# sevseg_driver.net
KiCad netlist of a schematic drawn in EAGLE
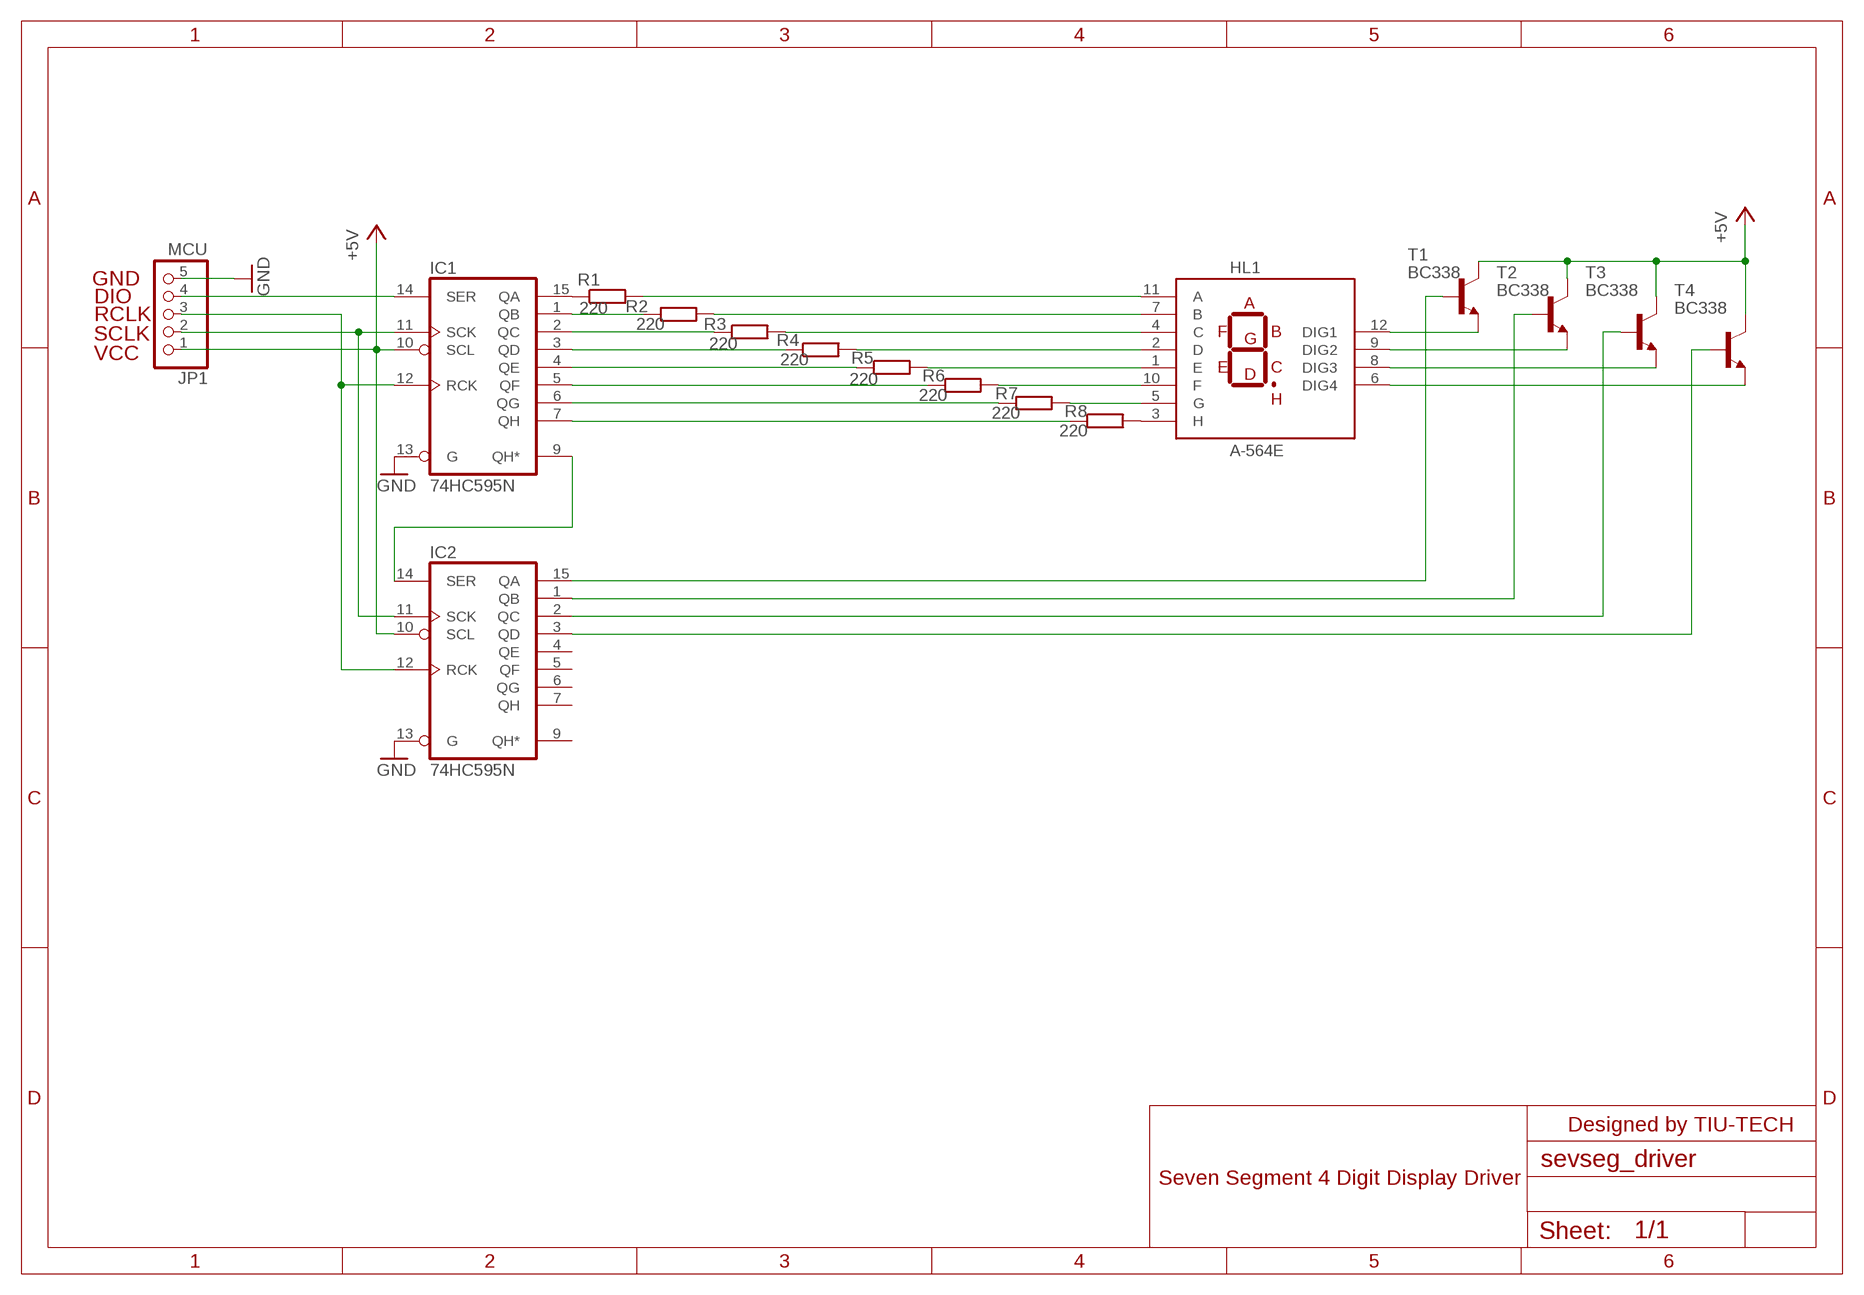
[diagram p0: schematic, sheet 1]

(export (version "E")
  (design (tool "Eeschema 10.0.6"))
  (components
    (comp (ref "HL1")
      (value "A-564E")
      (footprint "eagle-import:C_A-564")
      (libsource (lib "eagle-import") (part "A-564E"))
    )
    (comp (ref "IC1")
      (value "74HC595N")
      (footprint "eagle-import:DIL16")
      (libsource (lib "eagle-import") (part "74595NHC"))
    )
    (comp (ref "IC2")
      (value "74HC595N")
      (footprint "eagle-import:DIL16")
      (libsource (lib "eagle-import") (part "74595NHC"))
    )
    (comp (ref "JP1")
      (value "MCU")
      (footprint "eagle-import:1X05")
      (libsource (lib "eagle-import") (part "PINHD-1X5"))
    )
    (comp (ref "R1")
      (value "220")
      (footprint "eagle-import:0204_7")
      (libsource (lib "eagle-import") (part "R-EU_0204/7"))
    )
    (comp (ref "R2")
      (value "220")
      (footprint "eagle-import:0204_7")
      (libsource (lib "eagle-import") (part "R-EU_0204/7"))
    )
    (comp (ref "R3")
      (value "220")
      (footprint "eagle-import:0204_7")
      (libsource (lib "eagle-import") (part "R-EU_0204/7"))
    )
    (comp (ref "R4")
      (value "220")
      (footprint "eagle-import:0204_7")
      (libsource (lib "eagle-import") (part "R-EU_0204/7"))
    )
    (comp (ref "R5")
      (value "220")
      (footprint "eagle-import:0204_7")
      (libsource (lib "eagle-import") (part "R-EU_0204/7"))
    )
    (comp (ref "R6")
      (value "220")
      (footprint "eagle-import:0204_7")
      (libsource (lib "eagle-import") (part "R-EU_0204/7"))
    )
    (comp (ref "R7")
      (value "220")
      (footprint "eagle-import:0204_7")
      (libsource (lib "eagle-import") (part "R-EU_0204/7"))
    )
    (comp (ref "R8")
      (value "220")
      (footprint "eagle-import:0204_7")
      (libsource (lib "eagle-import") (part "R-EU_0204/7"))
    )
    (comp (ref "T1")
      (value "BC338")
      (footprint "eagle-import:TO92-EBC")
      (libsource (lib "eagle-import") (part "BC338"))
    )
    (comp (ref "T2")
      (value "BC338")
      (footprint "eagle-import:TO92-EBC")
      (libsource (lib "eagle-import") (part "BC338"))
    )
    (comp (ref "T3")
      (value "BC338")
      (footprint "eagle-import:TO92-EBC")
      (libsource (lib "eagle-import") (part "BC338"))
    )
    (comp (ref "T4")
      (value "BC338")
      (footprint "eagle-import:TO92-EBC")
      (libsource (lib "eagle-import") (part "BC338"))
    )
  )
  (nets
    (net (code "1") (name "+5V") (class "Default")
      (node (ref "IC1") (pin "10") (pinfunction "SCL_10") (pintype "input"))
      (node (ref "IC2") (pin "10") (pinfunction "SCL_10") (pintype "input"))
      (node (ref "JP1") (pin "1") (pinfunction "1_1") (pintype "passive"))
      (node (ref "T1") (pin "C") (pinfunction "C_C") (pintype "passive"))
      (node (ref "T2") (pin "C") (pinfunction "C_C") (pintype "passive"))
      (node (ref "T3") (pin "C") (pinfunction "C_C") (pintype "passive"))
      (node (ref "T4") (pin "C") (pinfunction "C_C") (pintype "passive"))
    )
    (net (code "2") (name "GND") (class "Default")
      (node (ref "IC1") (pin "13") (pinfunction "G_13") (pintype "input"))
      (node (ref "IC2") (pin "13") (pinfunction "G_13") (pintype "input"))
      (node (ref "JP1") (pin "5") (pinfunction "5_5") (pintype "passive"))
    )
    (net (code "3") (name "Net-(HL1-A)") (class "Default")
      (node (ref "HL1") (pin "11") (pinfunction "A_11") (pintype "input"))
      (node (ref "R1") (pin "2") (pinfunction "2_2") (pintype "passive"))
    )
    (net (code "4") (name "Net-(HL1-B)") (class "Default")
      (node (ref "HL1") (pin "7") (pinfunction "B_7") (pintype "input"))
      (node (ref "R2") (pin "2") (pinfunction "2_2") (pintype "passive"))
    )
    (net (code "5") (name "Net-(HL1-C)") (class "Default")
      (node (ref "HL1") (pin "4") (pinfunction "C_4") (pintype "input"))
      (node (ref "R3") (pin "2") (pinfunction "2_2") (pintype "passive"))
    )
    (net (code "6") (name "Net-(HL1-D)") (class "Default")
      (node (ref "HL1") (pin "2") (pinfunction "D_2") (pintype "input"))
      (node (ref "R4") (pin "2") (pinfunction "2_2") (pintype "passive"))
    )
    (net (code "7") (name "Net-(HL1-DIG1)") (class "Default")
      (node (ref "HL1") (pin "12") (pinfunction "DIG1_12") (pintype "input"))
      (node (ref "T1") (pin "E") (pinfunction "E_E") (pintype "passive"))
    )
    (net (code "8") (name "Net-(HL1-DIG2)") (class "Default")
      (node (ref "HL1") (pin "9") (pinfunction "DIG2_9") (pintype "input"))
      (node (ref "T2") (pin "E") (pinfunction "E_E") (pintype "passive"))
    )
    (net (code "9") (name "Net-(HL1-DIG3)") (class "Default")
      (node (ref "HL1") (pin "8") (pinfunction "DIG3_8") (pintype "input"))
      (node (ref "T3") (pin "E") (pinfunction "E_E") (pintype "passive"))
    )
    (net (code "10") (name "Net-(HL1-DIG4)") (class "Default")
      (node (ref "HL1") (pin "6") (pinfunction "DIG4_6") (pintype "input"))
      (node (ref "T4") (pin "E") (pinfunction "E_E") (pintype "passive"))
    )
    (net (code "11") (name "Net-(HL1-E)") (class "Default")
      (node (ref "HL1") (pin "1") (pinfunction "E_1") (pintype "input"))
      (node (ref "R5") (pin "2") (pinfunction "2_2") (pintype "passive"))
    )
    (net (code "12") (name "Net-(HL1-F)") (class "Default")
      (node (ref "HL1") (pin "10") (pinfunction "F_10") (pintype "input"))
      (node (ref "R6") (pin "2") (pinfunction "2_2") (pintype "passive"))
    )
    (net (code "13") (name "Net-(HL1-G)") (class "Default")
      (node (ref "HL1") (pin "5") (pinfunction "G_5") (pintype "input"))
      (node (ref "R7") (pin "2") (pinfunction "2_2") (pintype "passive"))
    )
    (net (code "14") (name "Net-(HL1-H)") (class "Default")
      (node (ref "HL1") (pin "3") (pinfunction "H_3") (pintype "input"))
      (node (ref "R8") (pin "2") (pinfunction "2_2") (pintype "passive"))
    )
    (net (code "15") (name "Net-(IC1A-QA)") (class "Default")
      (node (ref "IC1") (pin "15") (pinfunction "QA_15") (pintype "tri_state"))
      (node (ref "R1") (pin "1") (pinfunction "1_1") (pintype "passive"))
    )
    (net (code "16") (name "Net-(IC1A-QB)") (class "Default")
      (node (ref "IC1") (pin "1") (pinfunction "QB_1") (pintype "tri_state"))
      (node (ref "R2") (pin "1") (pinfunction "1_1") (pintype "passive"))
    )
    (net (code "17") (name "Net-(IC1A-QC)") (class "Default")
      (node (ref "IC1") (pin "2") (pinfunction "QC_2") (pintype "tri_state"))
      (node (ref "R3") (pin "1") (pinfunction "1_1") (pintype "passive"))
    )
    (net (code "18") (name "Net-(IC1A-QD)") (class "Default")
      (node (ref "IC1") (pin "3") (pinfunction "QD_3") (pintype "tri_state"))
      (node (ref "R4") (pin "1") (pinfunction "1_1") (pintype "passive"))
    )
    (net (code "19") (name "Net-(IC1A-QE)") (class "Default")
      (node (ref "IC1") (pin "4") (pinfunction "QE_4") (pintype "tri_state"))
      (node (ref "R5") (pin "1") (pinfunction "1_1") (pintype "passive"))
    )
    (net (code "20") (name "Net-(IC1A-QF)") (class "Default")
      (node (ref "IC1") (pin "5") (pinfunction "QF_5") (pintype "tri_state"))
      (node (ref "R6") (pin "1") (pinfunction "1_1") (pintype "passive"))
    )
    (net (code "21") (name "Net-(IC1A-QG)") (class "Default")
      (node (ref "IC1") (pin "6") (pinfunction "QG_6") (pintype "tri_state"))
      (node (ref "R7") (pin "1") (pinfunction "1_1") (pintype "passive"))
    )
    (net (code "22") (name "Net-(IC1A-QH)") (class "Default")
      (node (ref "IC1") (pin "7") (pinfunction "QH_7") (pintype "tri_state"))
      (node (ref "R8") (pin "1") (pinfunction "1_1") (pintype "passive"))
    )
    (net (code "23") (name "Net-(IC1A-QH*)") (class "Default")
      (node (ref "IC1") (pin "9") (pinfunction "QH*_9") (pintype "tri_state"))
      (node (ref "IC2") (pin "14") (pinfunction "SER_14") (pintype "input"))
    )
    (net (code "24") (name "Net-(IC1A-RCK)") (class "Default")
      (node (ref "IC1") (pin "12") (pinfunction "RCK_12") (pintype "input"))
      (node (ref "IC2") (pin "12") (pinfunction "RCK_12") (pintype "input"))
      (node (ref "JP1") (pin "3") (pinfunction "3_3") (pintype "passive"))
    )
    (net (code "25") (name "Net-(IC1A-SCK)") (class "Default")
      (node (ref "IC1") (pin "11") (pinfunction "SCK_11") (pintype "input"))
      (node (ref "IC2") (pin "11") (pinfunction "SCK_11") (pintype "input"))
      (node (ref "JP1") (pin "2") (pinfunction "2_2") (pintype "passive"))
    )
    (net (code "26") (name "Net-(IC1A-SER)") (class "Default")
      (node (ref "IC1") (pin "14") (pinfunction "SER_14") (pintype "input"))
      (node (ref "JP1") (pin "4") (pinfunction "4_4") (pintype "passive"))
    )
    (net (code "27") (name "Net-(IC2A-QA)") (class "Default")
      (node (ref "IC2") (pin "15") (pinfunction "QA_15") (pintype "tri_state"))
      (node (ref "T1") (pin "B") (pinfunction "B_B") (pintype "passive"))
    )
    (net (code "28") (name "Net-(IC2A-QB)") (class "Default")
      (node (ref "IC2") (pin "1") (pinfunction "QB_1") (pintype "tri_state"))
      (node (ref "T2") (pin "B") (pinfunction "B_B") (pintype "passive"))
    )
    (net (code "29") (name "Net-(IC2A-QC)") (class "Default")
      (node (ref "IC2") (pin "2") (pinfunction "QC_2") (pintype "tri_state"))
      (node (ref "T3") (pin "B") (pinfunction "B_B") (pintype "passive"))
    )
    (net (code "30") (name "Net-(IC2A-QD)") (class "Default")
      (node (ref "IC2") (pin "3") (pinfunction "QD_3") (pintype "tri_state"))
      (node (ref "T4") (pin "B") (pinfunction "B_B") (pintype "passive"))
    )
    (net (code "31") (name "unconnected-(IC2A-QE-Pad4)") (class "Default")
      (node (ref "IC2") (pin "4") (pinfunction "QE_4") (pintype "tri_state"))
    )
    (net (code "32") (name "unconnected-(IC2A-QF-Pad5)") (class "Default")
      (node (ref "IC2") (pin "5") (pinfunction "QF_5") (pintype "tri_state"))
    )
    (net (code "33") (name "unconnected-(IC2A-QG-Pad6)") (class "Default")
      (node (ref "IC2") (pin "6") (pinfunction "QG_6") (pintype "tri_state"))
    )
    (net (code "34") (name "unconnected-(IC2A-QH*-Pad9)") (class "Default")
      (node (ref "IC2") (pin "9") (pinfunction "QH*_9") (pintype "tri_state"))
    )
    (net (code "35") (name "unconnected-(IC2A-QH-Pad7)") (class "Default")
      (node (ref "IC2") (pin "7") (pinfunction "QH_7") (pintype "tri_state"))
    )
  )
)
